# exciting_voltage2.net
KiCad netlist of a schematic drawn in EAGLE
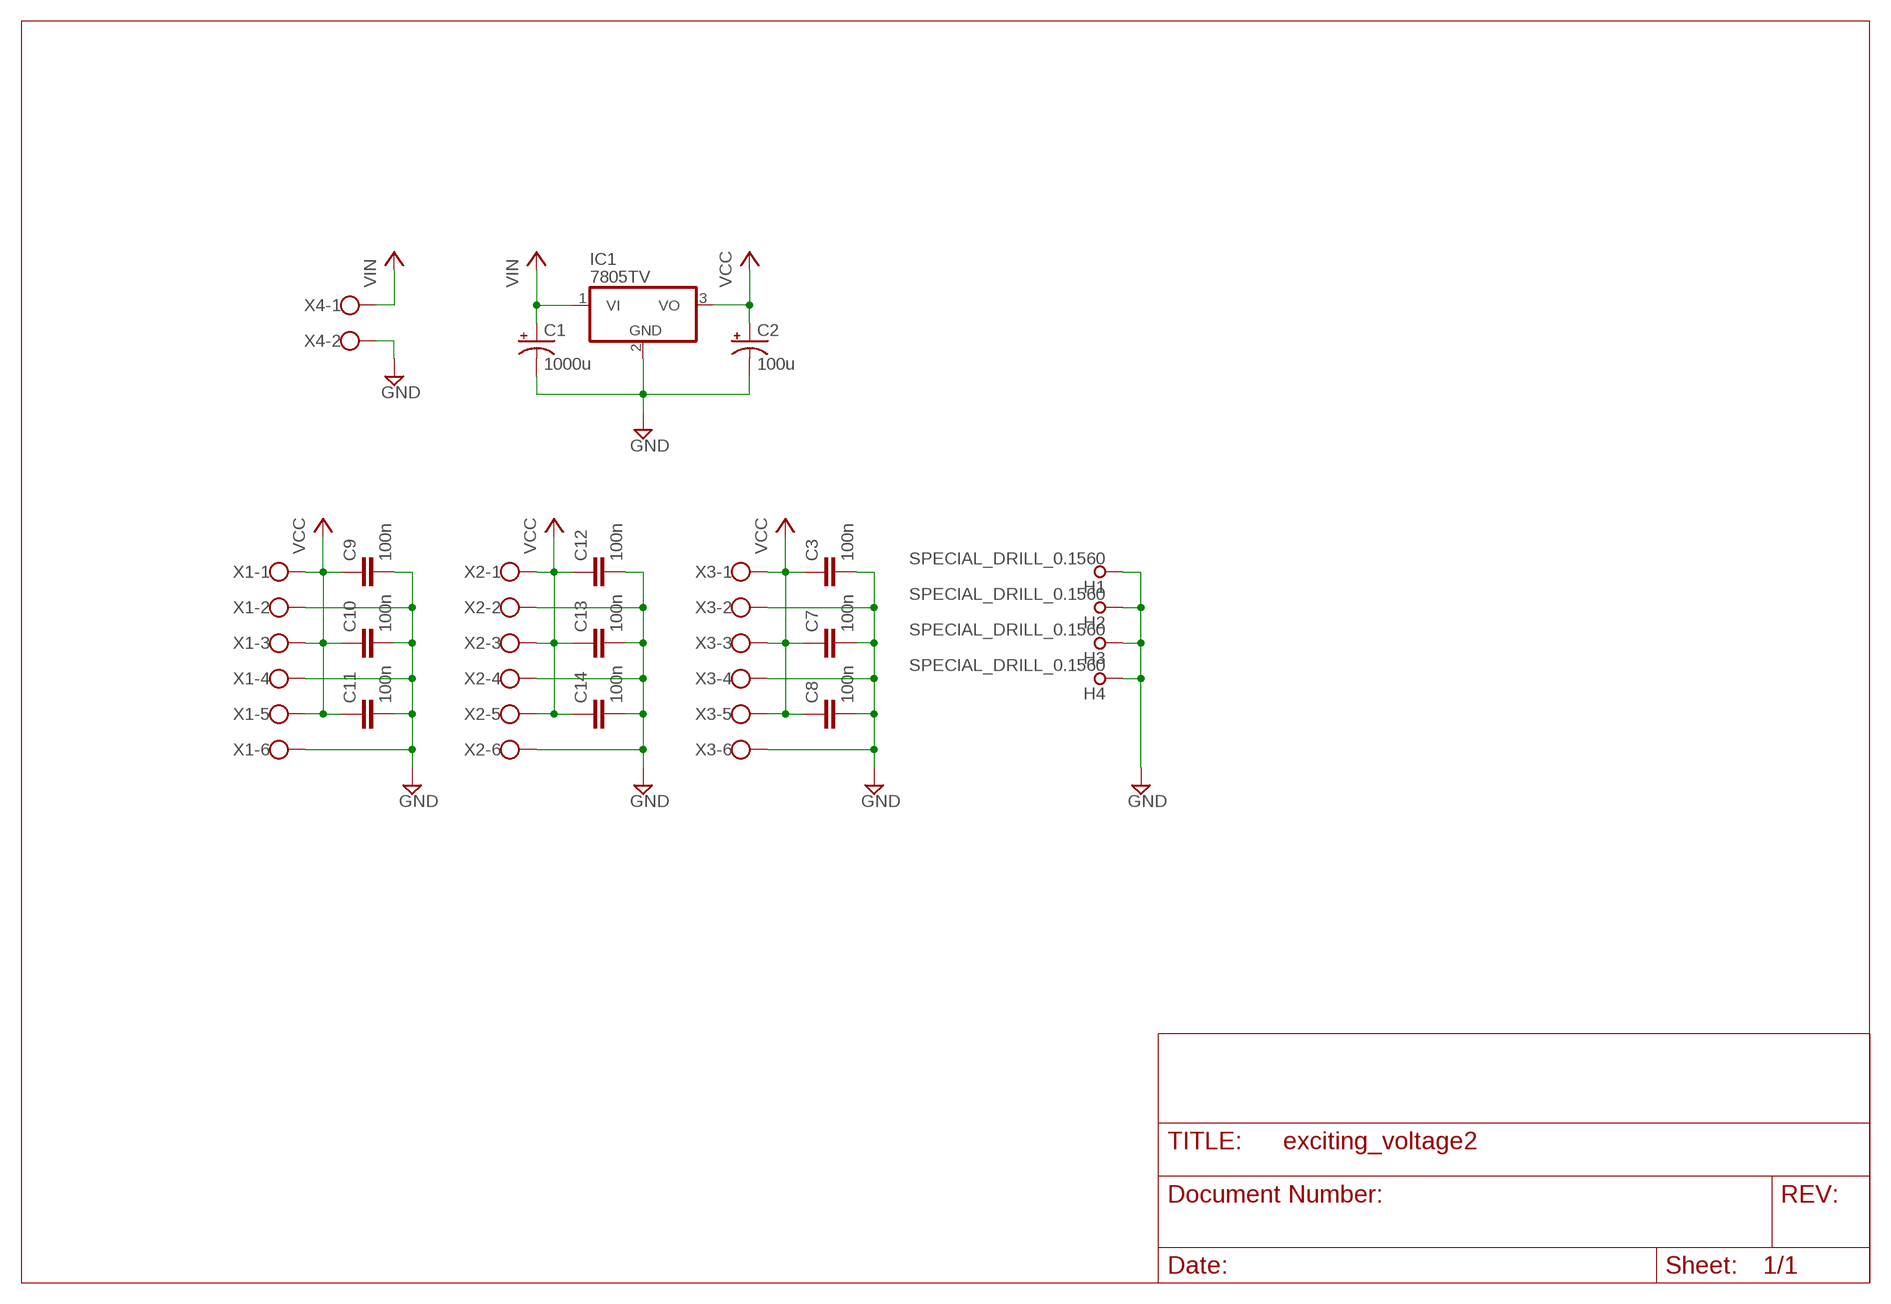
[diagram p0: schematic, sheet 1]

(export (version "E")
  (design (tool "Eeschema 10.0.6"))
  (components
    (comp (ref "C1")
      (value "1000u")
      (footprint "eagle-import:RCL_E5-13")
      (libsource (lib "eagle-import") (part "RCL_CPOL-USE5-13"))
    )
    (comp (ref "C2")
      (value "100u")
      (footprint "eagle-import:RCL_E2,5-7")
      (libsource (lib "eagle-import") (part "RCL_CPOL-USE2.5-7"))
    )
    (comp (ref "C3")
      (value "100n")
      (footprint "eagle-import:RCL_C050-025X075")
      (libsource (lib "eagle-import") (part "RCL_C-EU050-025X075"))
    )
    (comp (ref "C7")
      (value "100n")
      (footprint "eagle-import:RCL_C050-025X075")
      (libsource (lib "eagle-import") (part "RCL_C-EU050-025X075"))
    )
    (comp (ref "C8")
      (value "100n")
      (footprint "eagle-import:RCL_C050-025X075")
      (libsource (lib "eagle-import") (part "RCL_C-EU050-025X075"))
    )
    (comp (ref "C9")
      (value "100n")
      (footprint "eagle-import:RCL_C050-025X075")
      (libsource (lib "eagle-import") (part "RCL_C-EU050-025X075"))
    )
    (comp (ref "C10")
      (value "100n")
      (footprint "eagle-import:RCL_C050-025X075")
      (libsource (lib "eagle-import") (part "RCL_C-EU050-025X075"))
    )
    (comp (ref "C11")
      (value "100n")
      (footprint "eagle-import:RCL_C050-025X075")
      (libsource (lib "eagle-import") (part "RCL_C-EU050-025X075"))
    )
    (comp (ref "C12")
      (value "100n")
      (footprint "eagle-import:RCL_C050-025X075")
      (libsource (lib "eagle-import") (part "RCL_C-EU050-025X075"))
    )
    (comp (ref "C13")
      (value "100n")
      (footprint "eagle-import:RCL_C050-025X075")
      (libsource (lib "eagle-import") (part "RCL_C-EU050-025X075"))
    )
    (comp (ref "C14")
      (value "100n")
      (footprint "eagle-import:RCL_C050-025X075")
      (libsource (lib "eagle-import") (part "RCL_C-EU050-025X075"))
    )
    (comp (ref "H1")
      (value "SPECIAL_DRILL_0.1560")
      (footprint "eagle-import:PAD_0.1560")
      (libsource (lib "eagle-import") (part "SPECIAL_DRILL_0.1560"))
    )
    (comp (ref "H2")
      (value "SPECIAL_DRILL_0.1560")
      (footprint "eagle-import:PAD_0.1560")
      (libsource (lib "eagle-import") (part "SPECIAL_DRILL_0.1560"))
    )
    (comp (ref "H3")
      (value "SPECIAL_DRILL_0.1560")
      (footprint "eagle-import:PAD_0.1560")
      (libsource (lib "eagle-import") (part "SPECIAL_DRILL_0.1560"))
    )
    (comp (ref "H4")
      (value "SPECIAL_DRILL_0.1560")
      (footprint "eagle-import:PAD_0.1560")
      (libsource (lib "eagle-import") (part "SPECIAL_DRILL_0.1560"))
    )
    (comp (ref "IC1")
      (value "7805TV")
      (footprint "eagle-import:TO220V")
      (libsource (lib "eagle-import") (part "78TV05"))
    )
    (comp (ref "X1")
      (value "5EHDRC-6P")
      (footprint "eagle-import:5EHDRC-6P")
      (libsource (lib "eagle-import") (part "5EHDRC-6P"))
    )
    (comp (ref "X2")
      (value "5EHDRC-6P")
      (footprint "eagle-import:5EHDRC-6P")
      (libsource (lib "eagle-import") (part "5EHDRC-6P"))
    )
    (comp (ref "X3")
      (value "5EHDRC-6P")
      (footprint "eagle-import:5EHDRC-6P")
      (libsource (lib "eagle-import") (part "5EHDRC-6P"))
    )
    (comp (ref "X4")
      (value "5EHDRC-2P")
      (footprint "eagle-import:5EHDRC-2P")
      (libsource (lib "eagle-import") (part "5EHDRC-2P"))
    )
  )
  (nets
    (net (code "1") (name "GND") (class "Default")
      (node (ref "C1") (pin "-") (pinfunction "-_-") (pintype "passive"))
      (node (ref "C10") (pin "2") (pinfunction "2_2") (pintype "passive"))
      (node (ref "C11") (pin "2") (pinfunction "2_2") (pintype "passive"))
      (node (ref "C12") (pin "2") (pinfunction "2_2") (pintype "passive"))
      (node (ref "C13") (pin "2") (pinfunction "2_2") (pintype "passive"))
      (node (ref "C14") (pin "2") (pinfunction "2_2") (pintype "passive"))
      (node (ref "C2") (pin "-") (pinfunction "-_-") (pintype "passive"))
      (node (ref "C3") (pin "2") (pinfunction "2_2") (pintype "passive"))
      (node (ref "C7") (pin "2") (pinfunction "2_2") (pintype "passive"))
      (node (ref "C8") (pin "2") (pinfunction "2_2") (pintype "passive"))
      (node (ref "C9") (pin "2") (pinfunction "2_2") (pintype "passive"))
      (node (ref "H1") (pin "1") (pinfunction "1_1") (pintype "passive"))
      (node (ref "H2") (pin "1") (pinfunction "1_1") (pintype "passive"))
      (node (ref "H3") (pin "1") (pinfunction "1_1") (pintype "passive"))
      (node (ref "H4") (pin "1") (pinfunction "1_1") (pintype "passive"))
      (node (ref "IC1") (pin "2") (pinfunction "GND_2") (pintype "passive"))
      (node (ref "X1") (pin "2") (pinfunction "KL_2") (pintype "passive"))
      (node (ref "X1") (pin "4") (pinfunction "KL_4") (pintype "passive"))
      (node (ref "X1") (pin "6") (pinfunction "KL_6") (pintype "passive"))
      (node (ref "X2") (pin "2") (pinfunction "KL_2") (pintype "passive"))
      (node (ref "X2") (pin "4") (pinfunction "KL_4") (pintype "passive"))
      (node (ref "X2") (pin "6") (pinfunction "KL_6") (pintype "passive"))
      (node (ref "X3") (pin "2") (pinfunction "KL_2") (pintype "passive"))
      (node (ref "X3") (pin "4") (pinfunction "KL_4") (pintype "passive"))
      (node (ref "X3") (pin "6") (pinfunction "KL_6") (pintype "passive"))
      (node (ref "X4") (pin "2") (pinfunction "KL_2") (pintype "passive"))
    )
    (net (code "2") (name "VCC") (class "Default")
      (node (ref "C10") (pin "1") (pinfunction "1_1") (pintype "passive"))
      (node (ref "C11") (pin "1") (pinfunction "1_1") (pintype "passive"))
      (node (ref "C12") (pin "1") (pinfunction "1_1") (pintype "passive"))
      (node (ref "C13") (pin "1") (pinfunction "1_1") (pintype "passive"))
      (node (ref "C14") (pin "1") (pinfunction "1_1") (pintype "passive"))
      (node (ref "C2") (pin "+") (pinfunction "+_+") (pintype "passive"))
      (node (ref "C3") (pin "1") (pinfunction "1_1") (pintype "passive"))
      (node (ref "C7") (pin "1") (pinfunction "1_1") (pintype "passive"))
      (node (ref "C8") (pin "1") (pinfunction "1_1") (pintype "passive"))
      (node (ref "C9") (pin "1") (pinfunction "1_1") (pintype "passive"))
      (node (ref "IC1") (pin "3") (pinfunction "VO_3") (pintype "passive"))
      (node (ref "X1") (pin "1") (pinfunction "KL_1") (pintype "passive"))
      (node (ref "X1") (pin "3") (pinfunction "KL_3") (pintype "passive"))
      (node (ref "X1") (pin "5") (pinfunction "KL_5") (pintype "passive"))
      (node (ref "X2") (pin "1") (pinfunction "KL_1") (pintype "passive"))
      (node (ref "X2") (pin "3") (pinfunction "KL_3") (pintype "passive"))
      (node (ref "X2") (pin "5") (pinfunction "KL_5") (pintype "passive"))
      (node (ref "X3") (pin "1") (pinfunction "KL_1") (pintype "passive"))
      (node (ref "X3") (pin "3") (pinfunction "KL_3") (pintype "passive"))
      (node (ref "X3") (pin "5") (pinfunction "KL_5") (pintype "passive"))
    )
    (net (code "3") (name "VIN") (class "Default")
      (node (ref "C1") (pin "+") (pinfunction "+_+") (pintype "passive"))
      (node (ref "IC1") (pin "1") (pinfunction "VI_1") (pintype "input"))
      (node (ref "X4") (pin "1") (pinfunction "KL_1") (pintype "passive"))
    )
  )
)
